# NRF24L01_test_node.net
KiCad netlist of a schematic drawn in Altium Designer
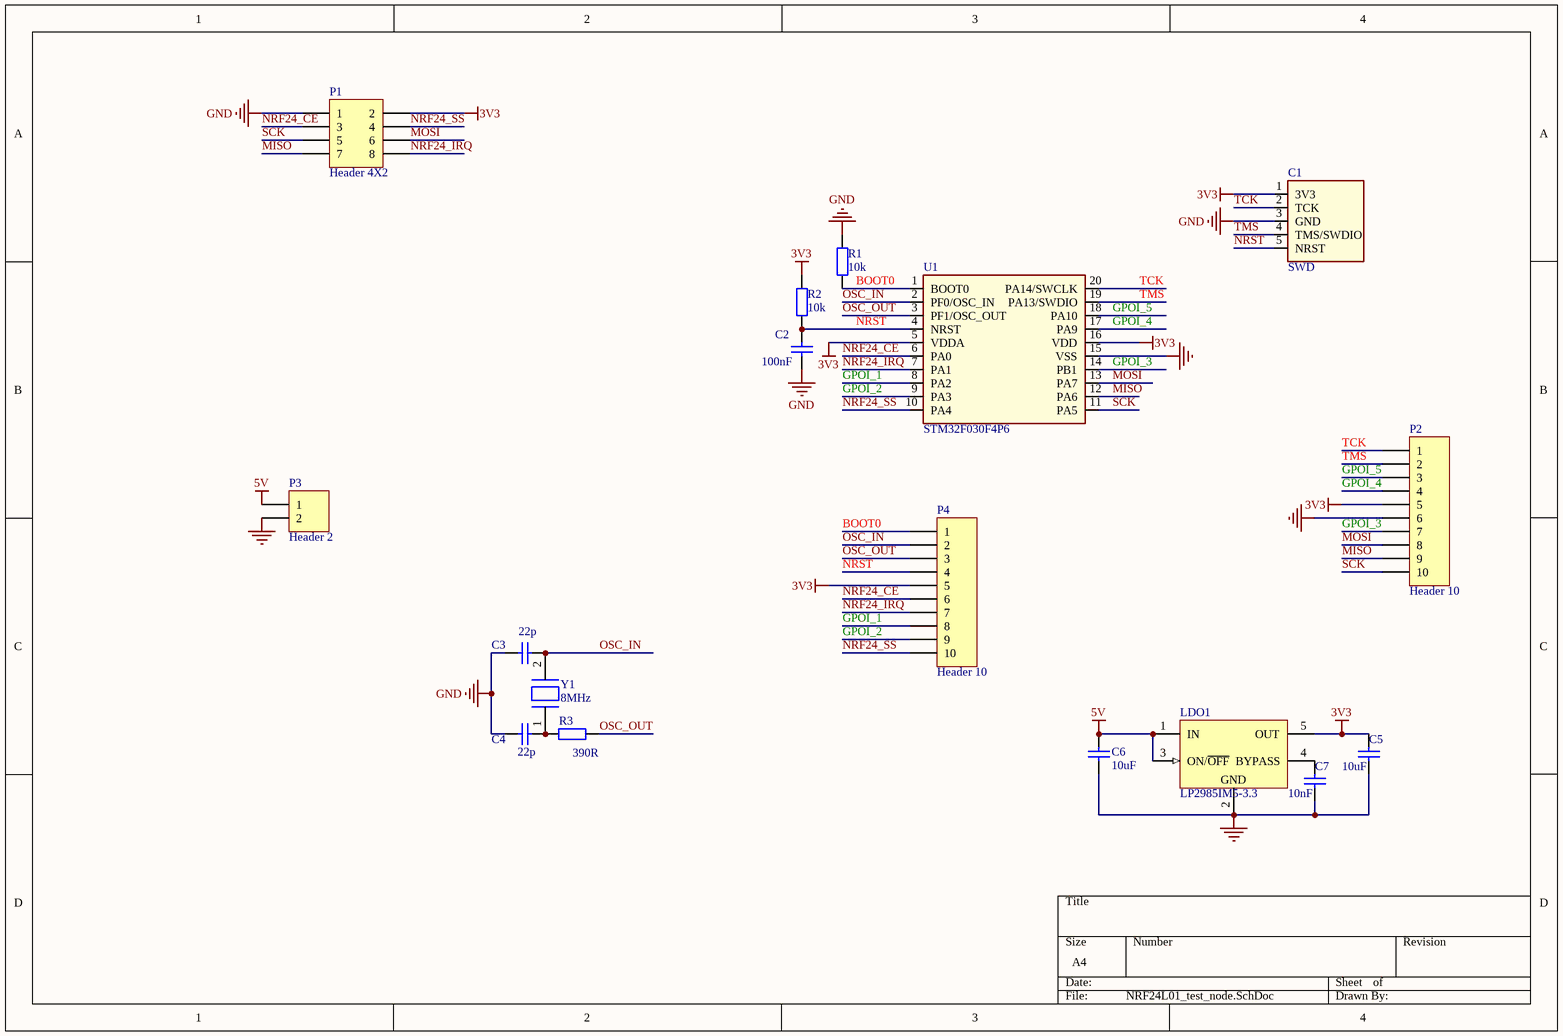
[diagram p0: NRF24L01_test_node.SchDoc]

(export (version "E")
  (design (tool "Eeschema 10.0.6"))
  (components
    (comp (ref "C1")
      (value "SWD")
      (footprint "SWD")
      (description "ARM SWD connector")
      (libsource (lib "Connector") (part "SWD"))
    )
    (comp (ref "C2")
      (value "100nF")
      (footprint "FP_0603_CAP_080")
      (description "Capacitor")
      (libsource (lib "Miscellaneous Devices") (part "Cap"))
    )
    (comp (ref "C3")
      (value "22p")
      (footprint "FP_0603_CAP_080")
      (description "Capacitor")
      (libsource (lib "Miscellaneous Devices") (part "Cap"))
    )
    (comp (ref "C4")
      (value "22p")
      (footprint "FP_0603_CAP_080")
      (description "Capacitor")
      (libsource (lib "Miscellaneous Devices") (part "Cap"))
    )
    (comp (ref "C5")
      (value "10uF")
      (footprint "FP_0603_CAP_080")
      (description "Capacitor")
      (libsource (lib "Miscellaneous Devices") (part "Cap"))
    )
    (comp (ref "C6")
      (value "10uF")
      (footprint "FP_0603_CAP_080")
      (description "Capacitor")
      (libsource (lib "Miscellaneous Devices") (part "Cap"))
    )
    (comp (ref "C7")
      (value "10nF")
      (footprint "FP_0603_CAP_080")
      (description "Capacitor")
      (libsource (lib "Miscellaneous Devices") (part "Cap"))
    )
    (comp (ref "LDO1")
      (value "LP2985IM5-3.3")
      (footprint "SUPPLY_SOT23-5")
      (description "Micropower 150 mA Ultra Low-Dropout Regulator In SOT-23/6 and micro SMD Packages")
      (libsource (lib "Supply") (part "LP2985"))
    )
    (comp (ref "P1")
      (value "Header 4X2")
      (footprint "FP_CONN8_SZK_ALLO")
      (description "Header, 4-Pin, Dual row")
      (fields (field (name "PUBLISHER") "Altium Limited"))
      (libsource (lib "Miscellaneous Connectors") (part "Header 4X2"))
    )
    (comp (ref "P2")
      (value "Header 10")
      (footprint "HDR1X10")
      (description "Header, 10-Pin")
      (fields (field (name "PUBLISHER") "Altium Limited"))
      (libsource (lib "Miscellaneous Connectors") (part "Header 10"))
    )
    (comp (ref "P3")
      (value "Header 2")
      (footprint "HDR1X2")
      (description "Header, 2-Pin")
      (fields (field (name "PUBLISHER") "Altium Limited"))
      (libsource (lib "Miscellaneous Connectors") (part "Header 2"))
    )
    (comp (ref "P4")
      (value "Header 10")
      (footprint "HDR1X10")
      (description "Header, 10-Pin")
      (fields (field (name "PUBLISHER") "Altium Limited"))
      (libsource (lib "Miscellaneous Connectors") (part "Header 10"))
    )
    (comp (ref "R1")
      (value "10k")
      (footprint "FP_0603_RES")
      (description "Resistor")
      (libsource (lib "Miscellaneous Devices") (part "Res3"))
    )
    (comp (ref "R2")
      (value "10k")
      (footprint "FP_0603_RES")
      (description "Resistor")
      (libsource (lib "Miscellaneous Devices") (part "Res3"))
    )
    (comp (ref "R3")
      (value "390R")
      (footprint "FP_0603_RES")
      (description "Resistor")
      (libsource (lib "") (part "Res3_1"))
    )
    (comp (ref "U1")
      (value "STM32F030F4P6")
      (footprint "uC_TSSOP20")
      (description "MCU 32-bit STM32F ARM Cortex M0 RISC 16KB Flash 2.5V/3.3V 20-Pin TSSOP")
      (libsource (lib "uC") (part "STM32F030F4P6"))
    )
    (comp (ref "Y1")
      (value "8MHz")
      (footprint "FP_CRYSTAL_HC49_SMD")
      (description "Standard HC49 quartz")
      (fields (field (name "Comment") "8MHz Quartz HC49"))
      (libsource (lib "Fufi_altium_lib") (part "XTAL HC49"))
    )
  )
  (nets
    (net (code "1") (name "/BOOT0") (class "Default")
      (node (ref "P4") (pin "1") (pinfunction "1_1") (pintype "passive"))
      (node (ref "R1") (pin "2") (pinfunction "2_2") (pintype "passive"))
      (node (ref "U1") (pin "1") (pinfunction "BOOT0_1") (pintype "passive"))
    )
    (net (code "2") (name "/GPOI_1") (class "Default")
      (node (ref "P4") (pin "8") (pinfunction "8_8") (pintype "passive"))
      (node (ref "U1") (pin "8") (pinfunction "PA2_8") (pintype "passive"))
    )
    (net (code "3") (name "/GPOI_2") (class "Default")
      (node (ref "P4") (pin "9") (pinfunction "9_9") (pintype "passive"))
      (node (ref "U1") (pin "9") (pinfunction "PA3_9") (pintype "passive"))
    )
    (net (code "4") (name "/GPOI_3") (class "Default")
      (node (ref "P2") (pin "7") (pinfunction "7_7") (pintype "passive"))
      (node (ref "U1") (pin "14") (pinfunction "PB1_14") (pintype "passive"))
    )
    (net (code "5") (name "/GPOI_4") (class "Default")
      (node (ref "P2") (pin "4") (pinfunction "4_4") (pintype "passive"))
      (node (ref "U1") (pin "17") (pinfunction "PA9_17") (pintype "passive"))
    )
    (net (code "6") (name "/GPOI_5") (class "Default")
      (node (ref "P2") (pin "3") (pinfunction "3_3") (pintype "passive"))
      (node (ref "U1") (pin "18") (pinfunction "PA10_18") (pintype "passive"))
    )
    (net (code "7") (name "/MISO") (class "Default")
      (node (ref "P1") (pin "7") (pinfunction "7_7") (pintype "passive"))
      (node (ref "P2") (pin "9") (pinfunction "9_9") (pintype "passive"))
      (node (ref "U1") (pin "12") (pinfunction "PA6_12") (pintype "passive"))
    )
    (net (code "8") (name "/MOSI") (class "Default")
      (node (ref "P1") (pin "6") (pinfunction "6_6") (pintype "passive"))
      (node (ref "P2") (pin "8") (pinfunction "8_8") (pintype "passive"))
      (node (ref "U1") (pin "13") (pinfunction "PA7_13") (pintype "passive"))
    )
    (net (code "9") (name "/NRF24_CE") (class "Default")
      (node (ref "P1") (pin "3") (pinfunction "3_3") (pintype "passive"))
      (node (ref "P4") (pin "6") (pinfunction "6_6") (pintype "passive"))
      (node (ref "U1") (pin "6") (pinfunction "PA0_6") (pintype "passive"))
    )
    (net (code "10") (name "/NRF24_IRQ") (class "Default")
      (node (ref "P1") (pin "8") (pinfunction "8_8") (pintype "passive"))
      (node (ref "P4") (pin "7") (pinfunction "7_7") (pintype "passive"))
      (node (ref "U1") (pin "7") (pinfunction "PA1_7") (pintype "passive"))
    )
    (net (code "11") (name "/NRF24_SS") (class "Default")
      (node (ref "P1") (pin "4") (pinfunction "4_4") (pintype "passive"))
      (node (ref "P4") (pin "10") (pinfunction "10_10") (pintype "passive"))
      (node (ref "U1") (pin "10") (pinfunction "PA4_10") (pintype "passive"))
    )
    (net (code "12") (name "/NRST") (class "Default")
      (node (ref "C1") (pin "5") (pinfunction "NRST_5") (pintype "passive"))
      (node (ref "C2") (pin "1") (pinfunction "1_1") (pintype "passive"))
      (node (ref "P4") (pin "4") (pinfunction "4_4") (pintype "passive"))
      (node (ref "R2") (pin "2") (pinfunction "2_2") (pintype "passive"))
      (node (ref "U1") (pin "4") (pinfunction "NRST_4") (pintype "passive"))
    )
    (net (code "13") (name "/OSC_IN") (class "Default")
      (node (ref "C3") (pin "2") (pinfunction "2_2") (pintype "passive"))
      (node (ref "P4") (pin "2") (pinfunction "2_2") (pintype "passive"))
      (node (ref "U1") (pin "2") (pinfunction "PF0/OSC_IN_2") (pintype "passive"))
      (node (ref "Y1") (pin "2") (pinfunction "2_2") (pintype "passive"))
    )
    (net (code "14") (name "/OSC_OUT") (class "Default")
      (node (ref "P4") (pin "3") (pinfunction "3_3") (pintype "passive"))
      (node (ref "R3") (pin "1") (pinfunction "1_1") (pintype "passive"))
      (node (ref "U1") (pin "3") (pinfunction "PF1/OSC_OUT_3") (pintype "passive"))
    )
    (net (code "15") (name "/SCK") (class "Default")
      (node (ref "P1") (pin "5") (pinfunction "5_5") (pintype "passive"))
      (node (ref "P2") (pin "10") (pinfunction "10_10") (pintype "passive"))
      (node (ref "U1") (pin "11") (pinfunction "PA5_11") (pintype "passive"))
    )
    (net (code "16") (name "/TCK") (class "Default")
      (node (ref "C1") (pin "2") (pinfunction "TCK_2") (pintype "passive"))
      (node (ref "P2") (pin "1") (pinfunction "1_1") (pintype "passive"))
      (node (ref "U1") (pin "20") (pinfunction "PA14/SWCLK_20") (pintype "passive"))
    )
    (net (code "17") (name "/TMS") (class "Default")
      (node (ref "C1") (pin "4") (pinfunction "TMS/SWDIO_4") (pintype "passive"))
      (node (ref "P2") (pin "2") (pinfunction "2_2") (pintype "passive"))
      (node (ref "U1") (pin "19") (pinfunction "PA13/SWDIO_19") (pintype "passive"))
    )
    (net (code "18") (name "3V3") (class "Default")
      (node (ref "C1") (pin "1") (pinfunction "3V3_1") (pintype "passive"))
      (node (ref "C5") (pin "2") (pinfunction "2_2") (pintype "passive"))
      (node (ref "LDO1") (pin "5") (pinfunction "OUT_5") (pintype "passive"))
      (node (ref "P1") (pin "2") (pinfunction "2_2") (pintype "passive"))
      (node (ref "P2") (pin "5") (pinfunction "5_5") (pintype "passive"))
      (node (ref "P4") (pin "5") (pinfunction "5_5") (pintype "passive"))
      (node (ref "R2") (pin "1") (pinfunction "1_1") (pintype "passive"))
      (node (ref "U1") (pin "16") (pinfunction "VDD_16") (pintype "passive"))
      (node (ref "U1") (pin "5") (pinfunction "VDDA_5") (pintype "passive"))
    )
    (net (code "19") (name "5V") (class "Default")
      (node (ref "C6") (pin "2") (pinfunction "2_2") (pintype "passive"))
      (node (ref "LDO1") (pin "1") (pinfunction "IN_1") (pintype "passive"))
      (node (ref "LDO1") (pin "3") (pinfunction "ON/~{OFF}_3") (pintype "input"))
      (node (ref "P3") (pin "1") (pinfunction "1_1") (pintype "passive"))
    )
    (net (code "20") (name "GND") (class "Default")
      (node (ref "C1") (pin "3") (pinfunction "GND_3") (pintype "passive"))
      (node (ref "C2") (pin "2") (pinfunction "2_2") (pintype "passive"))
      (node (ref "C3") (pin "1") (pinfunction "1_1") (pintype "passive"))
      (node (ref "C4") (pin "1") (pinfunction "1_1") (pintype "passive"))
      (node (ref "C5") (pin "1") (pinfunction "1_1") (pintype "passive"))
      (node (ref "C6") (pin "1") (pinfunction "1_1") (pintype "passive"))
      (node (ref "C7") (pin "1") (pinfunction "1_1") (pintype "passive"))
      (node (ref "LDO1") (pin "2") (pinfunction "GND_2") (pintype "passive"))
      (node (ref "P1") (pin "1") (pinfunction "1_1") (pintype "passive"))
      (node (ref "P2") (pin "6") (pinfunction "6_6") (pintype "passive"))
      (node (ref "P3") (pin "2") (pinfunction "2_2") (pintype "passive"))
      (node (ref "R1") (pin "1") (pinfunction "1_1") (pintype "passive"))
      (node (ref "U1") (pin "15") (pinfunction "VSS_15") (pintype "passive"))
    )
    (net (code "21") (name "Net-(C4-Pad2)") (class "Default")
      (node (ref "C4") (pin "2") (pinfunction "2_2") (pintype "passive"))
      (node (ref "R3") (pin "2") (pinfunction "2_2") (pintype "passive"))
      (node (ref "Y1") (pin "1") (pinfunction "1_1") (pintype "passive"))
    )
    (net (code "22") (name "Net-(LDO1-BYPASS)") (class "Default")
      (node (ref "C7") (pin "2") (pinfunction "2_2") (pintype "passive"))
      (node (ref "LDO1") (pin "4") (pinfunction "BYPASS_4") (pintype "passive"))
    )
  )
)
